# USBASP_Schematic.net
KiCad netlist of a schematic drawn in Altium Designer
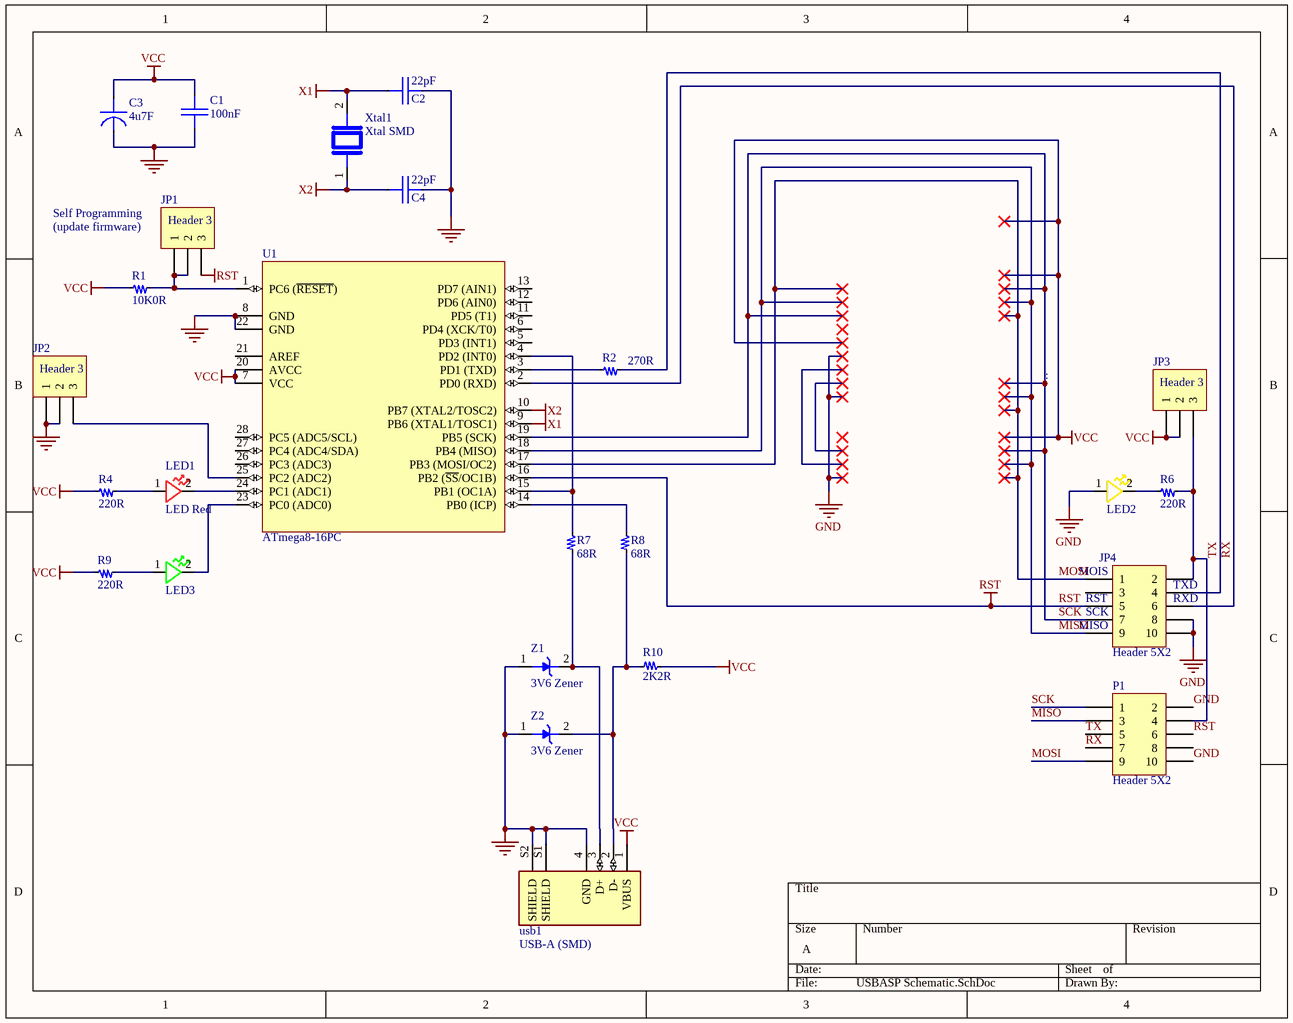
[diagram p0: USBASP Schematic.SchDoc]

(export (version "E")
  (design (tool "Eeschema 10.0.6"))
  (components
    (comp (ref "C1") (value "100nF") (footprint "SMD_0805") (libsource (lib "CAP's") (part "SMD CAP")))
    (comp (ref "C2") (value "22pF") (footprint "SMD_0805") (libsource (lib "CAP's") (part "SMD CAP")))
    (comp (ref "C3")
      (value "4u7F")
      (footprint "Core C (6.3X5.4)")
      (libsource (lib "CAP's") (part "Electrolit CAP"))
    )
    (comp (ref "C4") (value "22pF") (footprint "SMD_0805") (libsource (lib "CAP's") (part "SMD CAP")))
    (comp (ref "JP1")
      (value "Header 3")
      (footprint "HDR1X3")
      (description "Header, 3-Pin")
      (fields
        (field (name "ALTIUM_UNNAMED_1") "Self Programming")
        (field (name "ALTIUM_UNNAMED_2") "(update firmware)")
        (field (name "PUBLISHER") "Altium Limited")
      )
      (libsource (lib "Miscellaneous Connectors") (part "Header 3"))
    )
    (comp (ref "JP2")
      (value "Header 3")
      (footprint "HDR1X3")
      (description "Header, 3-Pin")
      (fields (field (name "PUBLISHER") "Altium Limited"))
      (libsource (lib "Miscellaneous Connectors") (part "Header 3"))
    )
    (comp (ref "JP3")
      (value "Header 3")
      (footprint "HDR1X3")
      (description "Header, 3-Pin")
      (fields (field (name "PUBLISHER") "Altium Limited"))
      (libsource (lib "Miscellaneous Connectors") (part "Header 3"))
    )
    (comp (ref "JP4")
      (value "Header 5X2")
      (footprint "HDR2X5")
      (description "Header, 5-Pin, Dual row")
      (fields
        (field (name "ALTIUM_UNNAMED_1") "MOIS")
        (field (name "ALTIUM_UNNAMED_3") "RST")
        (field (name "ALTIUM_UNNAMED_4") "SCK")
        (field (name "ALTIUM_UNNAMED_5") "MISO")
        (field (name "ALTIUM_UNNAMED_6") "TXD")
        (field (name "ALTIUM_UNNAMED_7") "RXD")
        (field (name "PUBLISHER") "Altium Limited")
      )
      (libsource (lib "Miscellaneous Connectors") (part "Header 5X2"))
    )
    (comp (ref "LED1")
      (value "LED Red")
      (footprint "LED 0805 RED")
      (libsource (lib "Diodes") (part "LED Red"))
    )
    (comp (ref "LED2")
      (value "LED Yellow")
      (footprint "LED 0805 YELLOW")
      (libsource (lib "Diodes") (part "LED Yellow"))
    )
    (comp (ref "LED3")
      (value "LED Green")
      (footprint "LED 0805 GREEN")
      (libsource (lib "Diodes") (part "LED Green"))
    )
    (comp (ref "P1")
      (value "Header 5X2")
      (footprint "HDR2X5")
      (description "Header, 5-Pin, Dual row")
      (fields (field (name "PUBLISHER") "Altium Limited"))
      (libsource (lib "Miscellaneous Connectors") (part "Header 5X2"))
    )
    (comp (ref "R1") (value "10K0R") (footprint "0805") (libsource (lib "RES") (part "SMD")))
    (comp (ref "R2") (value "270R") (footprint "0805") (libsource (lib "RES") (part "SMD")))
    (comp (ref "R4") (value "220R") (footprint "0805") (libsource (lib "RES") (part "SMD")))
    (comp (ref "R6") (value "220R") (footprint "0805") (libsource (lib "RES") (part "SMD")))
    (comp (ref "R7") (value "68R") (footprint "0805") (libsource (lib "RES") (part "SMD")))
    (comp (ref "R8") (value "68R") (footprint "0805") (libsource (lib "RES") (part "SMD")))
    (comp (ref "R9") (value "220R") (footprint "0805") (libsource (lib "RES") (part "SMD")))
    (comp (ref "R10") (value "2K2R") (footprint "0805") (libsource (lib "RES") (part "SMD")))
    (comp (ref "U1")
      (value "ATmega8-16PC")
      (footprint "AT MEGA 8")
      (description "8-Bit AVR Microcontroller with 8K Bytes of In-System Programmable Flash Memory")
      (fields (field (name "PUBLISHER") "Altium Limited"))
      (libsource (lib "Atmel Microcontroller 8-Bit AVR") (part "ATmega8-16PC"))
    )
    (comp (ref "usb1")
      (value "USB-A (SMD)")
      (footprint "USB-A (SMD)")
      (libsource (lib "Connectors") (part "USB-A (SMD)"))
    )
    (comp (ref "Xtal1") (value "Xtal SMD") (footprint "Xtal") (libsource (lib "IC's") (part "Xtal")))
    (comp (ref "Z1")
      (value "3V6 Zener")
      (footprint "Zener _ mini melf")
      (libsource (lib "Diodes") (part "Zener"))
    )
    (comp (ref "Z2")
      (value "3V6 Zener")
      (footprint "Zener _ mini melf")
      (libsource (lib "Diodes") (part "Zener"))
    )
  )
  (nets
    (net (code "1") (name "/MISO") (class "Default")
      (node (ref "JP4") (pin "9") (pinfunction "9_9") (pintype "passive"))
      (node (ref "P1") (pin "3") (pinfunction "3_3") (pintype "passive"))
      (node (ref "U1") (pin "18") (pinfunction "PB4_(MISO)_18") (pintype "bidirectional"))
    )
    (net (code "2") (name "/MOSI") (class "Default")
      (node (ref "JP4") (pin "1") (pinfunction "1_1") (pintype "passive"))
      (node (ref "P1") (pin "9") (pinfunction "9_9") (pintype "passive"))
      (node (ref "U1") (pin "17") (pinfunction "PB3_(MOSI/OC2)_17") (pintype "bidirectional"))
    )
    (net (code "3") (name "/RX") (class "Default")
      (node (ref "JP4") (pin "6") (pinfunction "6_6") (pintype "passive"))
      (node (ref "P1") (pin "7") (pinfunction "7_7") (pintype "passive"))
      (node (ref "U1") (pin "2") (pinfunction "PD0_(RXD)_2") (pintype "bidirectional"))
    )
    (net (code "4") (name "/SCK") (class "Default")
      (node (ref "JP4") (pin "7") (pinfunction "7_7") (pintype "passive"))
      (node (ref "P1") (pin "1") (pinfunction "1_1") (pintype "passive"))
      (node (ref "U1") (pin "19") (pinfunction "PB5_(SCK)_19") (pintype "bidirectional"))
    )
    (net (code "5") (name "/TX") (class "Default")
      (node (ref "JP4") (pin "4") (pinfunction "4_4") (pintype "passive"))
      (node (ref "P1") (pin "5") (pinfunction "5_5") (pintype "passive"))
      (node (ref "R2") (pin "1") (pinfunction "1_1") (pintype "passive"))
    )
    (net (code "6") (name "GND") (class "Default")
      (node (ref "C1") (pin "1") (pinfunction "1_1") (pintype "passive"))
      (node (ref "C2") (pin "2") (pinfunction "2_2") (pintype "passive"))
      (node (ref "C3") (pin "-") (pinfunction "-_-") (pintype "passive"))
      (node (ref "C4") (pin "2") (pinfunction "2_2") (pintype "passive"))
      (node (ref "JP2") (pin "1") (pinfunction "1_1") (pintype "passive"))
      (node (ref "JP2") (pin "2") (pinfunction "2_2") (pintype "passive"))
      (node (ref "JP4") (pin "10") (pinfunction "10_10") (pintype "passive"))
      (node (ref "JP4") (pin "8") (pinfunction "8_8") (pintype "passive"))
      (node (ref "LED2") (pin "1") (pinfunction "1_1") (pintype "passive"))
      (node (ref "P1") (pin "10") (pinfunction "10_10") (pintype "passive"))
      (node (ref "P1") (pin "2") (pinfunction "2_2") (pintype "passive"))
      (node (ref "U1") (pin "22") (pinfunction "GND_22") (pintype "power_in"))
      (node (ref "U1") (pin "8") (pinfunction "GND_8") (pintype "power_in"))
      (node (ref "Z1") (pin "1") (pinfunction "1_1") (pintype "passive"))
      (node (ref "Z2") (pin "1") (pinfunction "1_1") (pintype "passive"))
      (node (ref "usb1") (pin "4") (pinfunction "GND_4") (pintype "power_in"))
      (node (ref "usb1") (pin "S1") (pinfunction "SHIELD_S1") (pintype "power_in"))
      (node (ref "usb1") (pin "S2") (pinfunction "SHIELD_S2") (pintype "power_in"))
    )
    (net (code "7") (name "Net-(JP3-Pad3)") (class "Default")
      (node (ref "JP3") (pin "3") (pinfunction "3_3") (pintype "passive"))
      (node (ref "JP4") (pin "2") (pinfunction "2_2") (pintype "passive"))
      (node (ref "P1") (pin "4") (pinfunction "4_4") (pintype "passive"))
      (node (ref "R6") (pin "1") (pinfunction "1_1") (pintype "passive"))
    )
    (net (code "8") (name "Net-(LED1-Pad1)") (class "Default")
      (node (ref "LED1") (pin "1") (pinfunction "1_1") (pintype "passive"))
      (node (ref "R4") (pin "1") (pinfunction "1_1") (pintype "passive"))
    )
    (net (code "9") (name "Net-(LED2-Pad2)") (class "Default")
      (node (ref "LED2") (pin "2") (pinfunction "2_2") (pintype "passive"))
      (node (ref "R6") (pin "2") (pinfunction "2_2") (pintype "passive"))
    )
    (net (code "10") (name "Net-(LED3-Pad1)") (class "Default")
      (node (ref "LED3") (pin "1") (pinfunction "1_1") (pintype "passive"))
      (node (ref "R9") (pin "1") (pinfunction "1_1") (pintype "passive"))
    )
    (net (code "11") (name "Net-(U1-PB0_(ICP))") (class "Default")
      (node (ref "R8") (pin "2") (pinfunction "2_2") (pintype "passive"))
      (node (ref "U1") (pin "14") (pinfunction "PB0_(ICP)_14") (pintype "bidirectional"))
    )
    (net (code "12") (name "Net-(U1-PB1_(OC1A))") (class "Default")
      (node (ref "R7") (pin "2") (pinfunction "2_2") (pintype "passive"))
      (node (ref "U1") (pin "15") (pinfunction "PB1_(OC1A)_15") (pintype "bidirectional"))
      (node (ref "U1") (pin "4") (pinfunction "PD2_(INT0)_4") (pintype "bidirectional"))
    )
    (net (code "13") (name "Net-(U1-PC0_(ADC0))") (class "Default")
      (node (ref "LED3") (pin "2") (pinfunction "2_2") (pintype "passive"))
      (node (ref "U1") (pin "23") (pinfunction "PC0_(ADC0)_23") (pintype "bidirectional"))
    )
    (net (code "14") (name "Net-(U1-PC1_(ADC1))") (class "Default")
      (node (ref "LED1") (pin "2") (pinfunction "2_2") (pintype "passive"))
      (node (ref "U1") (pin "24") (pinfunction "PC1_(ADC1)_24") (pintype "bidirectional"))
    )
    (net (code "15") (name "Net-(U1-PC2_(ADC2))") (class "Default")
      (node (ref "JP2") (pin "3") (pinfunction "3_3") (pintype "passive"))
      (node (ref "U1") (pin "25") (pinfunction "PC2_(ADC2)_25") (pintype "bidirectional"))
    )
    (net (code "16") (name "Net-(U1-PC6_(~{RESET}))") (class "Default")
      (node (ref "JP1") (pin "1") (pinfunction "1_1") (pintype "passive"))
      (node (ref "JP1") (pin "2") (pinfunction "2_2") (pintype "passive"))
      (node (ref "R1") (pin "1") (pinfunction "1_1") (pintype "passive"))
      (node (ref "U1") (pin "1") (pinfunction "PC6_(~{RESET})_1") (pintype "bidirectional"))
    )
    (net (code "17") (name "Net-(U1-PD1_(TXD))") (class "Default")
      (node (ref "R2") (pin "2") (pinfunction "2_2") (pintype "passive"))
      (node (ref "U1") (pin "3") (pinfunction "PD1_(TXD)_3") (pintype "bidirectional"))
    )
    (net (code "18") (name "Net-(usb1-D+)") (class "Default")
      (node (ref "R7") (pin "1") (pinfunction "1_1") (pintype "passive"))
      (node (ref "Z1") (pin "2") (pinfunction "2_2") (pintype "passive"))
      (node (ref "usb1") (pin "3") (pinfunction "D+_3") (pintype "bidirectional"))
    )
    (net (code "19") (name "Net-(usb1-D-)") (class "Default")
      (node (ref "R10") (pin "1") (pinfunction "1_1") (pintype "passive"))
      (node (ref "R8") (pin "1") (pinfunction "1_1") (pintype "passive"))
      (node (ref "Z2") (pin "2") (pinfunction "2_2") (pintype "passive"))
      (node (ref "usb1") (pin "2") (pinfunction "D-_2") (pintype "bidirectional"))
    )
    (net (code "20") (name "RST") (class "Default")
      (node (ref "JP1") (pin "3") (pinfunction "3_3") (pintype "passive"))
      (node (ref "JP4") (pin "5") (pinfunction "5_5") (pintype "passive"))
      (node (ref "P1") (pin "6") (pinfunction "6_6") (pintype "passive"))
      (node (ref "U1") (pin "16") (pinfunction "PB2_(~{SS}/OC1B)_16") (pintype "bidirectional"))
    )
    (net (code "21") (name "VCC") (class "Default")
      (node (ref "C1") (pin "2") (pinfunction "2_2") (pintype "passive"))
      (node (ref "C3") (pin "+") (pinfunction "+_+") (pintype "passive"))
      (node (ref "JP3") (pin "1") (pinfunction "1_1") (pintype "passive"))
      (node (ref "JP3") (pin "2") (pinfunction "2_2") (pintype "passive"))
      (node (ref "R1") (pin "2") (pinfunction "2_2") (pintype "passive"))
      (node (ref "R10") (pin "2") (pinfunction "2_2") (pintype "passive"))
      (node (ref "R4") (pin "2") (pinfunction "2_2") (pintype "passive"))
      (node (ref "R9") (pin "2") (pinfunction "2_2") (pintype "passive"))
      (node (ref "U1") (pin "20") (pinfunction "AVCC_20") (pintype "power_in"))
      (node (ref "U1") (pin "7") (pinfunction "VCC_7") (pintype "power_in"))
      (node (ref "usb1") (pin "1") (pinfunction "VBUS_1") (pintype "power_in"))
    )
    (net (code "22") (name "X1") (class "Default")
      (node (ref "C2") (pin "1") (pinfunction "1_1") (pintype "passive"))
      (node (ref "U1") (pin "9") (pinfunction "PB6_(XTAL1/TOSC1)_9") (pintype "bidirectional"))
      (node (ref "Xtal1") (pin "2") (pinfunction "2_2") (pintype "passive"))
    )
    (net (code "23") (name "X2") (class "Default")
      (node (ref "C4") (pin "1") (pinfunction "1_1") (pintype "passive"))
      (node (ref "U1") (pin "10") (pinfunction "PB7_(XTAL2/TOSC2)_10") (pintype "bidirectional"))
      (node (ref "Xtal1") (pin "1") (pinfunction "1_1") (pintype "passive"))
    )
    (net (code "24") (name "unconnected-(JP4-Pad3)") (class "Default")
      (node (ref "JP4") (pin "3") (pinfunction "3_3") (pintype "passive"))
    )
    (net (code "25") (name "unconnected-(P1-Pad8)") (class "Default")
      (node (ref "P1") (pin "8") (pinfunction "8_8") (pintype "passive"))
    )
    (net (code "26") (name "unconnected-(U1-AREF-Pad21)") (class "Default")
      (node (ref "U1") (pin "21") (pinfunction "AREF_21") (pintype "passive"))
    )
    (net (code "27") (name "unconnected-(U1-PC3_(ADC3)-Pad26)") (class "Default")
      (node (ref "U1") (pin "26") (pinfunction "PC3_(ADC3)_26") (pintype "bidirectional"))
    )
    (net (code "28") (name "unconnected-(U1-PC4_(ADC4{slash}SDA)-Pad27)") (class "Default")
      (node (ref "U1") (pin "27") (pinfunction "PC4_(ADC4/SDA)_27") (pintype "bidirectional"))
    )
    (net (code "29") (name "unconnected-(U1-PC5_(ADC5{slash}SCL)-Pad28)") (class "Default")
      (node (ref "U1") (pin "28") (pinfunction "PC5_(ADC5/SCL)_28") (pintype "bidirectional"))
    )
    (net (code "30") (name "unconnected-(U1-PD3_(INT1)-Pad5)") (class "Default")
      (node (ref "U1") (pin "5") (pinfunction "PD3_(INT1)_5") (pintype "bidirectional"))
    )
    (net (code "31") (name "unconnected-(U1-PD4_(XCK{slash}T0)-Pad6)") (class "Default")
      (node (ref "U1") (pin "6") (pinfunction "PD4_(XCK/T0)_6") (pintype "bidirectional"))
    )
    (net (code "32") (name "unconnected-(U1-PD5_(T1)-Pad11)") (class "Default")
      (node (ref "U1") (pin "11") (pinfunction "PD5_(T1)_11") (pintype "bidirectional"))
    )
    (net (code "33") (name "unconnected-(U1-PD6_(AIN0)-Pad12)") (class "Default")
      (node (ref "U1") (pin "12") (pinfunction "PD6_(AIN0)_12") (pintype "bidirectional"))
    )
    (net (code "34") (name "unconnected-(U1-PD7_(AIN1)-Pad13)") (class "Default")
      (node (ref "U1") (pin "13") (pinfunction "PD7_(AIN1)_13") (pintype "bidirectional"))
    )
  )
)
